# Schematic_DRAFT.net
KiCad netlist of a schematic drawn in Altium Designer
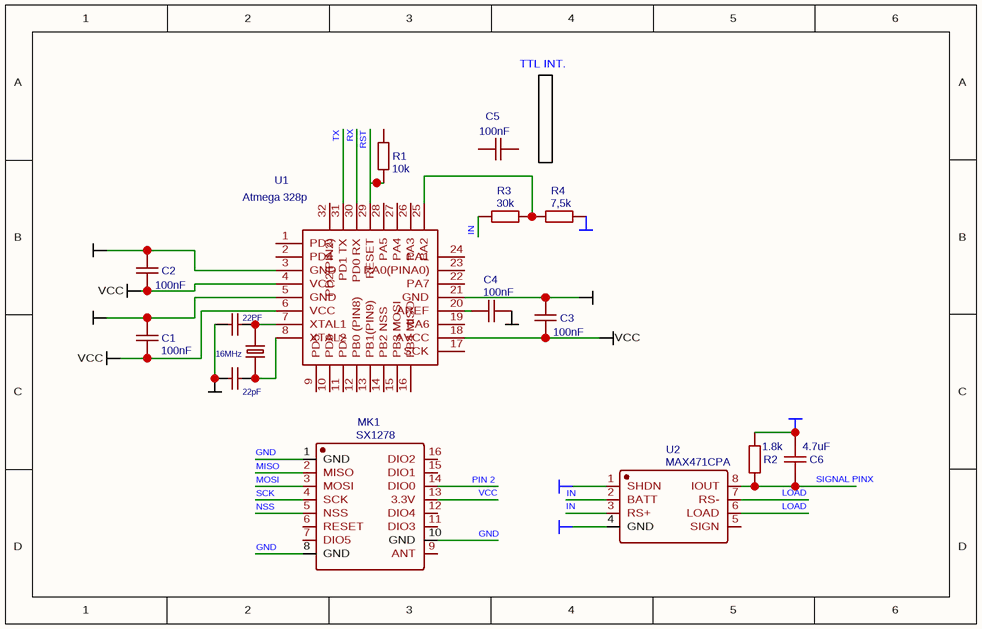
[diagram p0: Schematic DRAFT.schdoc]

(export (version "E")
  (design (tool "Eeschema 10.0.6"))
  (components
    (comp (ref "22PF")
      (value "100nF")
      (fields
        (field (name "BOM_MANUFACTURER PART") "Calibration capacitor100nF（104）100V,5%")
        (field (name "CONTRIBUTOR") "LCSC")
      )
      (libsource (lib "altium-import") (part "root_0__"))
    )
    (comp (ref "C1")
      (value "100nF")
      (fields
        (field (name "BOM_MANUFACTURER PART") "Calibration capacitor100nF（104）100V,5%")
        (field (name "CONTRIBUTOR") "LCSC")
      )
      (libsource (lib "altium-import") (part "root_1__"))
    )
    (comp (ref "C2")
      (value "100nF")
      (fields
        (field (name "BOM_MANUFACTURER PART") "Calibration capacitor100nF（104）100V,5%")
        (field (name "CONTRIBUTOR") "LCSC")
      )
      (libsource (lib "altium-import") (part "root_1__"))
    )
    (comp (ref "C3")
      (value "100nF")
      (fields
        (field (name "BOM_MANUFACTURER PART") "Calibration capacitor100nF（104）100V,5%")
        (field (name "CONTRIBUTOR") "LCSC")
      )
      (libsource (lib "altium-import") (part "root_1__"))
    )
    (comp (ref "C4")
      (value "100nF")
      (fields
        (field (name "BOM_MANUFACTURER PART") "Calibration capacitor100nF（104）100V,5%")
        (field (name "CONTRIBUTOR") "LCSC")
      )
      (libsource (lib "altium-import") (part "root_0__"))
    )
    (comp (ref "C5")
      (value "100nF")
      (fields
        (field (name "BOM_MANUFACTURER PART") "Calibration capacitor100nF（104）100V,5%")
        (field (name "CONTRIBUTOR") "LCSC")
      )
      (libsource (lib "altium-import") (part "root_0__"))
    )
    (comp (ref "C6")
      (value "4.7uF")
      (fields (field (name "BOM_MANUFACTURER PART") "?"))
      (libsource (lib "") (part "root_0___3"))
    )
    (comp (ref "C7")
      (value "22pF")
      (fields
        (field (name "BOM_MANUFACTURER PART") "Calibration capacitor100nF（104）100V,5%")
        (field (name "CONTRIBUTOR") "LCSC")
      )
      (libsource (lib "altium-import") (part "root_0__"))
    )
    (comp (ref "MK1")
      (value "SX1278")
      (fields (field (name "CONTRIBUTOR") "LCSC"))
      (libsource (lib "") (part "root_0___2"))
    )
    (comp (ref "R1")
      (value "10k")
      (fields (field (name "BOM_MANUFACTURER PART") "?"))
      (libsource (lib "altium-import") (part "root_3__"))
    )
    (comp (ref "R2")
      (value "1.8k")
      (fields (field (name "BOM_MANUFACTURER PART") "?"))
      (libsource (lib "") (part "root_1___1"))
    )
    (comp (ref "R3")
      (value "30k")
      (fields (field (name "BOM_MANUFACTURER PART") "?"))
      (libsource (lib "") (part "root_0___5"))
    )
    (comp (ref "R4")
      (value "7,5k")
      (fields (field (name "BOM_MANUFACTURER PART") "?"))
      (libsource (lib "") (part "root_0___5"))
    )
    (comp (ref "U1")
      (value "Atmega 328p")
      (fields
        (field (name "BOM_MANUFACTURER PART") "Atmega 328p smd")
        (field (name "CONTRIBUTOR") "rienkvandenberg")
      )
      (libsource (lib "") (part "root_0___4"))
    )
    (comp (ref "U2")
      (value "MAX471CPA")
      (fields (field (name "BOM_MANUFACTURER PART") "?"))
      (libsource (lib "") (part "root_0___1"))
    )
    (comp (ref "X1")
      (value "16MHz")
      (fields
        (field (name "BOM_MANUFACTURER PART") "HC-49SM16MHz20pF30ppm")
        (field (name "CONTRIBUTOR") "LCSC")
      )
      (libsource (lib "") (part "root_1___2"))
    )
  )
  (nets
    (net (code "1") (name "GND") (class "Default")
      (node (ref "22PF") (pin "1") (pinfunction "1_1") (pintype "passive"))
      (node (ref "C1") (pin "2") (pinfunction "2_2") (pintype "passive"))
      (node (ref "C2") (pin "2") (pinfunction "2_2") (pintype "passive"))
      (node (ref "C3") (pin "2") (pinfunction "2_2") (pintype "passive"))
      (node (ref "C4") (pin "2") (pinfunction "2_2") (pintype "passive"))
      (node (ref "C6") (pin "2") (pinfunction "2_2") (pintype "passive"))
      (node (ref "C7") (pin "1") (pinfunction "1_1") (pintype "passive"))
      (node (ref "R2") (pin "2") (pinfunction "2_2") (pintype "passive"))
      (node (ref "R4") (pin "2") (pinfunction "2_2") (pintype "passive"))
      (node (ref "U1") (pin "21") (pinfunction "GND_21") (pintype "passive"))
      (node (ref "U1") (pin "3") (pinfunction "GND_3") (pintype "passive"))
      (node (ref "U1") (pin "5") (pinfunction "GND_5") (pintype "passive"))
      (node (ref "U2") (pin "1") (pinfunction "SHDN_1") (pintype "passive"))
      (node (ref "U2") (pin "4") (pinfunction "GND_4") (pintype "passive"))
    )
    (net (code "2") (name "Net-(U1-AREF)") (class "Default")
      (node (ref "C4") (pin "1") (pinfunction "1_1") (pintype "passive"))
      (node (ref "U1") (pin "20") (pinfunction "AREF_20") (pintype "passive"))
    )
    (net (code "3") (name "Net-(U1-PA2)") (class "Default")
      (node (ref "R3") (pin "2") (pinfunction "2_2") (pintype "passive"))
      (node (ref "R4") (pin "1") (pinfunction "1_1") (pintype "passive"))
      (node (ref "U1") (pin "25") (pinfunction "PA2_25") (pintype "passive"))
    )
    (net (code "4") (name "Net-(U1-RESET)") (class "Default")
      (node (ref "R1") (pin "2") (pinfunction "2_2") (pintype "passive"))
      (node (ref "U1") (pin "29") (pinfunction "RESET_29") (pintype "passive"))
    )
    (net (code "5") (name "Net-(U1-XTAL1)") (class "Default")
      (node (ref "22PF") (pin "2") (pinfunction "2_2") (pintype "passive"))
      (node (ref "U1") (pin "7") (pinfunction "XTAL1_7") (pintype "passive"))
      (node (ref "X1") (pin "2") (pinfunction "2_2") (pintype "passive"))
    )
    (net (code "6") (name "Net-(U1-XTAL2)") (class "Default")
      (node (ref "C7") (pin "2") (pinfunction "2_2") (pintype "passive"))
      (node (ref "U1") (pin "8") (pinfunction "XTAL2_8") (pintype "passive"))
      (node (ref "X1") (pin "1") (pinfunction "1_1") (pintype "passive"))
    )
    (net (code "7") (name "Net-(U2-IOUT)") (class "Default")
      (node (ref "C6") (pin "1") (pinfunction "1_1") (pintype "passive"))
      (node (ref "R2") (pin "1") (pinfunction "1_1") (pintype "passive"))
      (node (ref "U2") (pin "8") (pinfunction "IOUT_8") (pintype "passive"))
    )
    (net (code "8") (name "VCC") (class "Default")
      (node (ref "C1") (pin "1") (pinfunction "1_1") (pintype "passive"))
      (node (ref "C2") (pin "1") (pinfunction "1_1") (pintype "passive"))
      (node (ref "C3") (pin "1") (pinfunction "1_1") (pintype "passive"))
      (node (ref "U1") (pin "18") (pinfunction "AVCC_18") (pintype "passive"))
      (node (ref "U1") (pin "4") (pinfunction "VCC_4") (pintype "passive"))
      (node (ref "U1") (pin "6") (pinfunction "VCC_6") (pintype "passive"))
    )
    (net (code "9") (name "unconnected-(C5-Pad1)") (class "Default")
      (node (ref "C5") (pin "1") (pinfunction "1_1") (pintype "passive"))
    )
    (net (code "10") (name "unconnected-(C5-Pad2)") (class "Default")
      (node (ref "C5") (pin "2") (pinfunction "2_2") (pintype "passive"))
    )
    (net (code "11") (name "unconnected-(MK1-3.3V-Pad13)") (class "Default")
      (node (ref "MK1") (pin "13") (pinfunction "3.3V_13") (pintype "passive"))
    )
    (net (code "12") (name "unconnected-(MK1-ANT-Pad9)") (class "Default")
      (node (ref "MK1") (pin "9") (pinfunction "ANT_9") (pintype "passive"))
    )
    (net (code "13") (name "unconnected-(MK1-DIO0-Pad14)") (class "Default")
      (node (ref "MK1") (pin "14") (pinfunction "DIO0_14") (pintype "passive"))
    )
    (net (code "14") (name "unconnected-(MK1-DIO1-Pad15)") (class "Default")
      (node (ref "MK1") (pin "15") (pinfunction "DIO1_15") (pintype "passive"))
    )
    (net (code "15") (name "unconnected-(MK1-DIO2-Pad16)") (class "Default")
      (node (ref "MK1") (pin "16") (pinfunction "DIO2_16") (pintype "passive"))
    )
    (net (code "16") (name "unconnected-(MK1-DIO3-Pad11)") (class "Default")
      (node (ref "MK1") (pin "11") (pinfunction "DIO3_11") (pintype "passive"))
    )
    (net (code "17") (name "unconnected-(MK1-DIO4-Pad12)") (class "Default")
      (node (ref "MK1") (pin "12") (pinfunction "DIO4_12") (pintype "passive"))
    )
    (net (code "18") (name "unconnected-(MK1-DIO5-Pad7)") (class "Default")
      (node (ref "MK1") (pin "7") (pinfunction "DIO5_7") (pintype "passive"))
    )
    (net (code "19") (name "unconnected-(MK1-GND-Pad1)") (class "Default")
      (node (ref "MK1") (pin "1") (pinfunction "GND_1") (pintype "passive"))
    )
    (net (code "20") (name "unconnected-(MK1-GND-Pad8)") (class "Default")
      (node (ref "MK1") (pin "8") (pinfunction "GND_8") (pintype "passive"))
    )
    (net (code "21") (name "unconnected-(MK1-GND-Pad10)") (class "Default")
      (node (ref "MK1") (pin "10") (pinfunction "GND_10") (pintype "passive"))
    )
    (net (code "22") (name "unconnected-(MK1-MISO-Pad2)") (class "Default")
      (node (ref "MK1") (pin "2") (pinfunction "MISO_2") (pintype "passive"))
    )
    (net (code "23") (name "unconnected-(MK1-MOSI-Pad3)") (class "Default")
      (node (ref "MK1") (pin "3") (pinfunction "MOSI_3") (pintype "passive"))
    )
    (net (code "24") (name "unconnected-(MK1-NSS-Pad5)") (class "Default")
      (node (ref "MK1") (pin "5") (pinfunction "NSS_5") (pintype "passive"))
    )
    (net (code "25") (name "unconnected-(MK1-RESET-Pad6)") (class "Default")
      (node (ref "MK1") (pin "6") (pinfunction "RESET_6") (pintype "passive"))
    )
    (net (code "26") (name "unconnected-(MK1-SCK-Pad4)") (class "Default")
      (node (ref "MK1") (pin "4") (pinfunction "SCK_4") (pintype "passive"))
    )
    (net (code "27") (name "unconnected-(R1-Pad1)") (class "Default")
      (node (ref "R1") (pin "1") (pinfunction "1_1") (pintype "passive"))
    )
    (net (code "28") (name "unconnected-(R3-Pad1)") (class "Default")
      (node (ref "R3") (pin "1") (pinfunction "1_1") (pintype "passive"))
    )
    (net (code "29") (name "unconnected-(U1-PA0(PINA0)-Pad23)") (class "Default")
      (node (ref "U1") (pin "23") (pinfunction "PA0(PINA0)_23") (pintype "passive"))
    )
    (net (code "30") (name "unconnected-(U1-PA1-Pad24)") (class "Default")
      (node (ref "U1") (pin "24") (pinfunction "PA1_24") (pintype "passive"))
    )
    (net (code "31") (name "unconnected-(U1-PA3-Pad26)") (class "Default")
      (node (ref "U1") (pin "26") (pinfunction "PA3_26") (pintype "passive"))
    )
    (net (code "32") (name "unconnected-(U1-PA4-Pad27)") (class "Default")
      (node (ref "U1") (pin "27") (pinfunction "PA4_27") (pintype "passive"))
    )
    (net (code "33") (name "unconnected-(U1-PA5-Pad28)") (class "Default")
      (node (ref "U1") (pin "28") (pinfunction "PA5_28") (pintype "passive"))
    )
    (net (code "34") (name "unconnected-(U1-PA6-Pad19)") (class "Default")
      (node (ref "U1") (pin "19") (pinfunction "PA6_19") (pintype "passive"))
    )
    (net (code "35") (name "unconnected-(U1-PA7-Pad22)") (class "Default")
      (node (ref "U1") (pin "22") (pinfunction "PA7_22") (pintype "passive"))
    )
    (net (code "36") (name "unconnected-(U1-PB0_(PIN8)-Pad12)") (class "Default")
      (node (ref "U1") (pin "12") (pinfunction "PB0_(PIN8)_12") (pintype "passive"))
    )
    (net (code "37") (name "unconnected-(U1-PB1(PIN9)-Pad13)") (class "Default")
      (node (ref "U1") (pin "13") (pinfunction "PB1(PIN9)_13") (pintype "passive"))
    )
    (net (code "38") (name "unconnected-(U1-PB2_NSS-Pad14)") (class "Default")
      (node (ref "U1") (pin "14") (pinfunction "PB2_NSS_14") (pintype "passive"))
    )
    (net (code "39") (name "unconnected-(U1-PB3_MOSI-Pad15)") (class "Default")
      (node (ref "U1") (pin "15") (pinfunction "PB3_MOSI_15") (pintype "passive"))
    )
    (net (code "40") (name "unconnected-(U1-PB4_MISO-Pad16)") (class "Default")
      (node (ref "U1") (pin "16") (pinfunction "PB4_MISO_16") (pintype "passive"))
    )
    (net (code "41") (name "unconnected-(U1-PD0_RX-Pad30)") (class "Default")
      (node (ref "U1") (pin "30") (pinfunction "PD0_RX_30") (pintype "passive"))
    )
    (net (code "42") (name "unconnected-(U1-PD1_TX-Pad31)") (class "Default")
      (node (ref "U1") (pin "31") (pinfunction "PD1_TX_31") (pintype "passive"))
    )
    (net (code "43") (name "unconnected-(U1-PD2(PIN2)-Pad32)") (class "Default")
      (node (ref "U1") (pin "32") (pinfunction "PD2(PIN2)_32") (pintype "passive"))
    )
    (net (code "44") (name "unconnected-(U1-PD3-Pad1)") (class "Default")
      (node (ref "U1") (pin "1") (pinfunction "PD3_1") (pintype "passive"))
    )
    (net (code "45") (name "unconnected-(U1-PD4-Pad2)") (class "Default")
      (node (ref "U1") (pin "2") (pinfunction "PD4_2") (pintype "passive"))
    )
    (net (code "46") (name "unconnected-(U1-PD5-Pad9)") (class "Default")
      (node (ref "U1") (pin "9") (pinfunction "PD5_9") (pintype "passive"))
    )
    (net (code "47") (name "unconnected-(U1-PD6-Pad10)") (class "Default")
      (node (ref "U1") (pin "10") (pinfunction "PD6_10") (pintype "passive"))
    )
    (net (code "48") (name "unconnected-(U1-PD7-Pad11)") (class "Default")
      (node (ref "U1") (pin "11") (pinfunction "PD7_11") (pintype "passive"))
    )
    (net (code "49") (name "unconnected-(U1-SCK-Pad17)") (class "Default")
      (node (ref "U1") (pin "17") (pinfunction "SCK_17") (pintype "passive"))
    )
    (net (code "50") (name "unconnected-(U2-BATT-Pad2)") (class "Default")
      (node (ref "U2") (pin "2") (pinfunction "BATT_2") (pintype "passive"))
    )
    (net (code "51") (name "unconnected-(U2-LOAD-Pad6)") (class "Default")
      (node (ref "U2") (pin "6") (pinfunction "LOAD_6") (pintype "passive"))
    )
    (net (code "52") (name "unconnected-(U2-RS+-Pad3)") (class "Default")
      (node (ref "U2") (pin "3") (pinfunction "RS+_3") (pintype "passive"))
    )
    (net (code "53") (name "unconnected-(U2-RS--Pad7)") (class "Default")
      (node (ref "U2") (pin "7") (pinfunction "RS-_7") (pintype "passive"))
    )
    (net (code "54") (name "unconnected-(U2-SIGN-Pad5)") (class "Default")
      (node (ref "U2") (pin "5") (pinfunction "SIGN_5") (pintype "passive"))
    )
  )
)
